# ClockGenerator.net
KiCad netlist of a schematic drawn in Altium Designer
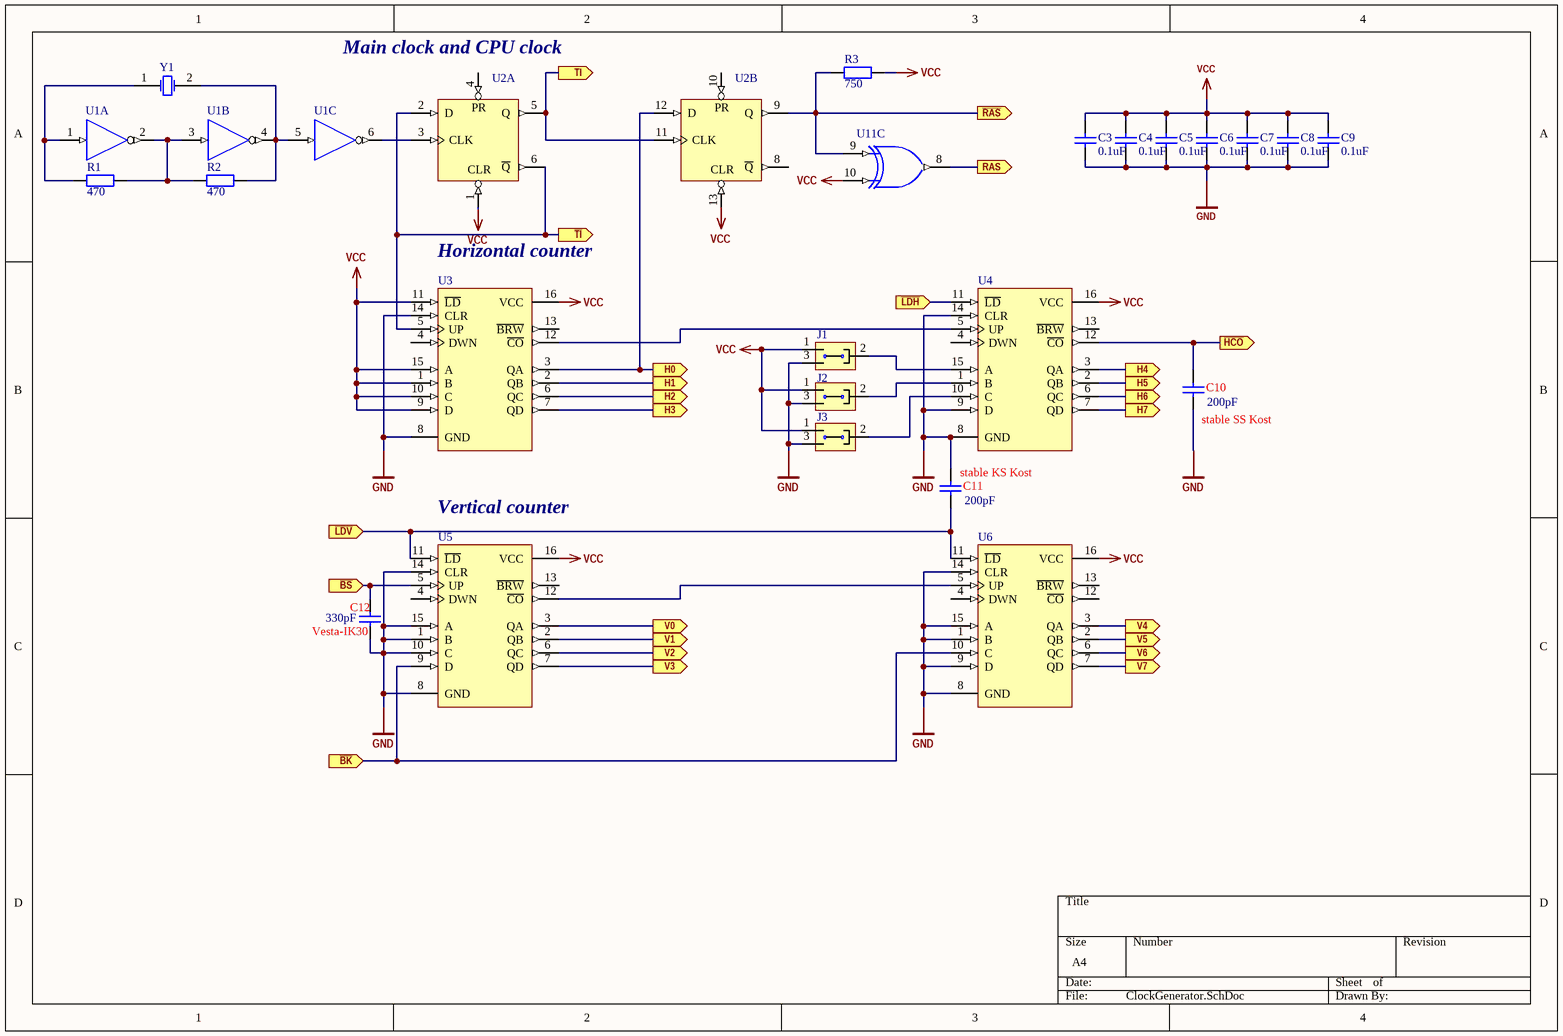
[diagram p0: ClockGenerator.SchDoc]

(export (version "E")
  (design (tool "Eeschema 10.0.6"))
  (components
    (comp (ref "C3")
      (value "0.1uF")
      (footprint "RAD-0.3")
      (description "Capacitor")
      (fields (field (name "Comment") "Cap") (field (name "PUBLISHER") "Altium Limited"))
      (libsource (lib "Lenin") (part "Cap"))
    )
    (comp (ref "C4")
      (value "0.1uF")
      (footprint "RAD-0.3")
      (description "Capacitor")
      (fields (field (name "Comment") "Cap") (field (name "PUBLISHER") "Altium Limited"))
      (libsource (lib "Lenin") (part "Cap"))
    )
    (comp (ref "C5")
      (value "0.1uF")
      (footprint "RAD-0.3")
      (description "Capacitor")
      (fields (field (name "Comment") "Cap") (field (name "PUBLISHER") "Altium Limited"))
      (libsource (lib "Lenin") (part "Cap"))
    )
    (comp (ref "C6")
      (value "0.1uF")
      (footprint "RAD-0.3")
      (description "Capacitor")
      (fields (field (name "Comment") "Cap") (field (name "PUBLISHER") "Altium Limited"))
      (libsource (lib "Lenin") (part "Cap"))
    )
    (comp (ref "C7")
      (value "0.1uF")
      (footprint "RAD-0.3")
      (description "Capacitor")
      (fields (field (name "Comment") "Cap") (field (name "PUBLISHER") "Altium Limited"))
      (libsource (lib "Lenin") (part "Cap"))
    )
    (comp (ref "C8")
      (value "0.1uF")
      (footprint "RAD-0.3")
      (description "Capacitor")
      (fields (field (name "Comment") "Cap") (field (name "PUBLISHER") "Altium Limited"))
      (libsource (lib "Lenin") (part "Cap"))
    )
    (comp (ref "C9")
      (value "0.1uF")
      (footprint "RAD-0.3")
      (description "Capacitor")
      (fields (field (name "Comment") "Cap") (field (name "PUBLISHER") "Altium Limited"))
      (libsource (lib "Lenin") (part "Cap"))
    )
    (comp (ref "C10")
      (value "stable SS Kost")
      (footprint "RAD-0.3")
      (description "Capacitor")
      (fields (field (name "ALTIUM_VALUE") "200pF") (field (name "PUBLISHER") "Altium Limited"))
      (libsource (lib "Lenin") (part "Cap"))
    )
    (comp (ref "C11")
      (value "stable KS Kost")
      (footprint "RAD-0.3")
      (description "Capacitor")
      (fields (field (name "ALTIUM_VALUE") "200pF") (field (name "PUBLISHER") "Altium Limited"))
      (libsource (lib "Lenin") (part "Cap"))
    )
    (comp (ref "C12")
      (value "Vesta-IK30")
      (footprint "RAD-0.3")
      (description "Capacitor")
      (fields (field (name "ALTIUM_VALUE") "330pF") (field (name "PUBLISHER") "Altium Limited"))
      (libsource (lib "Lenin") (part "Cap"))
    )
    (comp (ref "J1")
      (value "Jump3")
      (footprint "Miscellaneous Connectors:MHDR1X3")
      (libsource (lib "Lenin") (part "Jump3"))
    )
    (comp (ref "J2")
      (value "Jump3")
      (footprint "Miscellaneous Connectors:MHDR1X3")
      (libsource (lib "Lenin") (part "Jump3"))
    )
    (comp (ref "J3")
      (value "Jump3")
      (footprint "Miscellaneous Connectors:MHDR1X3")
      (libsource (lib "Lenin") (part "Jump3"))
    )
    (comp (ref "R1")
      (value "470")
      (footprint "Lenin:AXIAL-0.4")
      (description "Resistor")
      (fields (field (name "PUBLISHER") "Altium Limited"))
      (libsource (lib "Lenin") (part "Res2"))
    )
    (comp (ref "R2")
      (value "470")
      (footprint "Lenin:AXIAL-0.4")
      (description "Resistor")
      (fields (field (name "PUBLISHER") "Altium Limited"))
      (libsource (lib "Lenin") (part "Res2"))
    )
    (comp (ref "R3")
      (value "750")
      (footprint "Lenin:AXIAL-0.4")
      (description "Resistor")
      (fields (field (name "PUBLISHER") "Altium Limited"))
      (libsource (lib "Lenin") (part "Res2"))
    )
    (comp (ref "U1")
      (value "~")
      (footprint "N014")
      (description "Hex Inverter")
      (fields (field (name "PUBLISHER") "Altium Limited"))
      (libsource (lib "TI Logic Gate 2") (part "SN74HC04N"))
    )
    (comp (ref "U2")
      (value "~")
      (footprint "N014")
      (description "Dual D-Type Positive-Edge-Triggered Flip-Flop with Clear and Preset")
      (fields (field (name "PUBLISHER") "Altium Limited"))
      (libsource (lib "TI Logic Flip-Flop") (part "SN74HC74N"))
    )
    (comp (ref "U3")
      (value "~")
      (footprint "N016")
      (description "4-Bit Synchronous Up/Down Counter (Dual Clock with Clear)")
      (fields (field (name "PUBLISHER") "Altium Limited"))
      (libsource (lib "TI Logic Counter") (part "SN74HC193N"))
    )
    (comp (ref "U4")
      (value "~")
      (footprint "N016")
      (description "4-Bit Synchronous Up/Down Counter (Dual Clock with Clear)")
      (fields (field (name "PUBLISHER") "Altium Limited"))
      (libsource (lib "TI Logic Counter") (part "SN74HC193N"))
    )
    (comp (ref "U5")
      (value "~")
      (footprint "N016")
      (description "4-Bit Synchronous Up/Down Counter (Dual Clock with Clear)")
      (fields (field (name "PUBLISHER") "Altium Limited"))
      (libsource (lib "TI Logic Counter") (part "SN74HC193N"))
    )
    (comp (ref "U6")
      (value "~")
      (footprint "N016")
      (description "4-Bit Synchronous Up/Down Counter (Dual Clock with Clear)")
      (fields (field (name "PUBLISHER") "Altium Limited"))
      (libsource (lib "TI Logic Counter") (part "SN74HC193N"))
    )
    (comp (ref "U11")
      (value "~")
      (footprint "N014")
      (description "Quadruple 2-Input Exclusive-OR Gate")
      (fields (field (name "PUBLISHER") "Altium Limited"))
      (libsource (lib "TI Logic Gate 2") (part "SN74HC86N"))
    )
    (comp (ref "Y1")
      (value "XTAL")
      (footprint "Lenin:HC25U")
      (description "Crystal Oscillator")
      (fields (field (name "PUBLISHER") "Altium Limited"))
      (libsource (lib "Lenin") (part "XTAL"))
    )
  )
  (nets
    (net (code "1") (name "/H0") (class "Default")
      (node (ref "U2") (pin "12") (pinfunction "D_12") (pintype "input"))
      (node (ref "U3") (pin "3") (pinfunction "QA_3") (pintype "output"))
    )
    (net (code "2") (name "/H1") (class "Default")
      (node (ref "U3") (pin "2") (pinfunction "QB_2") (pintype "output"))
    )
    (net (code "3") (name "/H2") (class "Default")
      (node (ref "U3") (pin "6") (pinfunction "QC_6") (pintype "output"))
    )
    (net (code "4") (name "/H3") (class "Default")
      (node (ref "U3") (pin "7") (pinfunction "QD_7") (pintype "output"))
    )
    (net (code "5") (name "/H4") (class "Default")
      (node (ref "U4") (pin "3") (pinfunction "QA_3") (pintype "output"))
    )
    (net (code "6") (name "/H5") (class "Default")
      (node (ref "U4") (pin "2") (pinfunction "QB_2") (pintype "output"))
    )
    (net (code "7") (name "/H6") (class "Default")
      (node (ref "U4") (pin "6") (pinfunction "QC_6") (pintype "output"))
    )
    (net (code "8") (name "/H7") (class "Default")
      (node (ref "U4") (pin "7") (pinfunction "QD_7") (pintype "output"))
    )
    (net (code "9") (name "/RAS") (class "Default")
      (node (ref "U11") (pin "8") (pinfunction "Y_8") (pintype "output"))
    )
    (net (code "10") (name "/TI") (class "Default")
      (node (ref "U2") (pin "11") (pinfunction "CLK_11") (pintype "input"))
      (node (ref "U2") (pin "5") (pinfunction "Q_5") (pintype "output"))
    )
    (net (code "11") (name "/V0") (class "Default")
      (node (ref "U5") (pin "3") (pinfunction "QA_3") (pintype "output"))
    )
    (net (code "12") (name "/V1") (class "Default")
      (node (ref "U5") (pin "2") (pinfunction "QB_2") (pintype "output"))
    )
    (net (code "13") (name "/V2") (class "Default")
      (node (ref "U5") (pin "6") (pinfunction "QC_6") (pintype "output"))
    )
    (net (code "14") (name "/V3") (class "Default")
      (node (ref "U5") (pin "7") (pinfunction "QD_7") (pintype "output"))
    )
    (net (code "15") (name "/V4") (class "Default")
      (node (ref "U6") (pin "3") (pinfunction "QA_3") (pintype "output"))
    )
    (net (code "16") (name "/V5") (class "Default")
      (node (ref "U6") (pin "2") (pinfunction "QB_2") (pintype "output"))
    )
    (net (code "17") (name "/V6") (class "Default")
      (node (ref "U6") (pin "6") (pinfunction "QC_6") (pintype "output"))
    )
    (net (code "18") (name "/V7") (class "Default")
      (node (ref "U6") (pin "7") (pinfunction "QD_7") (pintype "output"))
    )
    (net (code "19") (name "/~{BK}") (class "Default")
      (node (ref "U5") (pin "9") (pinfunction "D_9") (pintype "input"))
      (node (ref "U6") (pin "10") (pinfunction "C_10") (pintype "input"))
    )
    (net (code "20") (name "/~{BS}") (class "Default")
      (node (ref "C12") (pin "2") (pinfunction "2_2") (pintype "passive"))
      (node (ref "U5") (pin "5") (pinfunction "UP_5") (pintype "input"))
    )
    (net (code "21") (name "/~{HCO}") (class "Default")
      (node (ref "C10") (pin "2") (pinfunction "2_2") (pintype "passive"))
      (node (ref "U4") (pin "12") (pinfunction "~{CO}_12") (pintype "output"))
    )
    (net (code "22") (name "/~{LDH}") (class "Default")
      (node (ref "U4") (pin "11") (pinfunction "~{LD}_11") (pintype "input"))
    )
    (net (code "23") (name "/~{LDV}") (class "Default")
      (node (ref "C11") (pin "1") (pinfunction "1_1") (pintype "passive"))
      (node (ref "U5") (pin "11") (pinfunction "~{LD}_11") (pintype "input"))
      (node (ref "U6") (pin "11") (pinfunction "~{LD}_11") (pintype "input"))
    )
    (net (code "24") (name "/~{RAS}") (class "Default")
      (node (ref "R3") (pin "1") (pinfunction "1_1") (pintype "passive"))
      (node (ref "U11") (pin "9") (pinfunction "A_9") (pintype "input"))
      (node (ref "U2") (pin "9") (pinfunction "Q_9") (pintype "output"))
    )
    (net (code "25") (name "/~{TI}") (class "Default")
      (node (ref "U2") (pin "2") (pinfunction "D_2") (pintype "input"))
      (node (ref "U2") (pin "6") (pinfunction "~{Q}_6") (pintype "output"))
      (node (ref "U3") (pin "5") (pinfunction "UP_5") (pintype "input"))
    )
    (net (code "26") (name "GND") (class "Default")
      (node (ref "C10") (pin "1") (pinfunction "1_1") (pintype "passive"))
      (node (ref "C11") (pin "2") (pinfunction "2_2") (pintype "passive"))
      (node (ref "C12") (pin "1") (pinfunction "1_1") (pintype "passive"))
      (node (ref "C3") (pin "1") (pinfunction "1_1") (pintype "passive"))
      (node (ref "C4") (pin "1") (pinfunction "1_1") (pintype "passive"))
      (node (ref "C5") (pin "1") (pinfunction "1_1") (pintype "passive"))
      (node (ref "C6") (pin "1") (pinfunction "1_1") (pintype "passive"))
      (node (ref "C7") (pin "1") (pinfunction "1_1") (pintype "passive"))
      (node (ref "C8") (pin "1") (pinfunction "1_1") (pintype "passive"))
      (node (ref "C9") (pin "1") (pinfunction "1_1") (pintype "passive"))
      (node (ref "J1") (pin "3") (pintype "passive"))
      (node (ref "J2") (pin "3") (pintype "passive"))
      (node (ref "J3") (pin "3") (pintype "passive"))
      (node (ref "U1") (pin "7") (pinfunction "GND_7") (pintype "power_in"))
      (node (ref "U11") (pin "7") (pinfunction "GND_7") (pintype "power_in"))
      (node (ref "U2") (pin "7") (pinfunction "GND_7") (pintype "power_in"))
      (node (ref "U3") (pin "14") (pinfunction "CLR_14") (pintype "input"))
      (node (ref "U3") (pin "8") (pinfunction "GND_8") (pintype "power_in"))
      (node (ref "U4") (pin "14") (pinfunction "CLR_14") (pintype "input"))
      (node (ref "U4") (pin "8") (pinfunction "GND_8") (pintype "power_in"))
      (node (ref "U4") (pin "9") (pinfunction "D_9") (pintype "input"))
      (node (ref "U5") (pin "1") (pinfunction "B_1") (pintype "input"))
      (node (ref "U5") (pin "10") (pinfunction "C_10") (pintype "input"))
      (node (ref "U5") (pin "14") (pinfunction "CLR_14") (pintype "input"))
      (node (ref "U5") (pin "15") (pinfunction "A_15") (pintype "input"))
      (node (ref "U5") (pin "8") (pinfunction "GND_8") (pintype "power_in"))
      (node (ref "U6") (pin "1") (pinfunction "B_1") (pintype "input"))
      (node (ref "U6") (pin "14") (pinfunction "CLR_14") (pintype "input"))
      (node (ref "U6") (pin "15") (pinfunction "A_15") (pintype "input"))
      (node (ref "U6") (pin "8") (pinfunction "GND_8") (pintype "power_in"))
      (node (ref "U6") (pin "9") (pinfunction "D_9") (pintype "input"))
    )
    (net (code "27") (name "Net-(U1A-A)") (class "Default")
      (node (ref "R1") (pin "1") (pinfunction "1_1") (pintype "passive"))
      (node (ref "U1") (pin "1") (pinfunction "A_1") (pintype "input"))
      (node (ref "Y1") (pin "1") (pinfunction "OSC1_1") (pintype "passive"))
    )
    (net (code "28") (name "Net-(U1A-Y)") (class "Default")
      (node (ref "R1") (pin "2") (pinfunction "2_2") (pintype "passive"))
      (node (ref "R2") (pin "1") (pinfunction "1_1") (pintype "passive"))
      (node (ref "U1") (pin "2") (pinfunction "Y_2") (pintype "output"))
      (node (ref "U1") (pin "3") (pinfunction "A_3") (pintype "input"))
    )
    (net (code "29") (name "Net-(U1B-Y)") (class "Default")
      (node (ref "R2") (pin "2") (pinfunction "2_2") (pintype "passive"))
      (node (ref "U1") (pin "4") (pinfunction "Y_4") (pintype "output"))
      (node (ref "U1") (pin "5") (pinfunction "A_5") (pintype "input"))
      (node (ref "Y1") (pin "2") (pinfunction "OSC2_2") (pintype "passive"))
    )
    (net (code "30") (name "Net-(U1C-Y)") (class "Default")
      (node (ref "U1") (pin "6") (pinfunction "Y_6") (pintype "output"))
      (node (ref "U2") (pin "3") (pinfunction "CLK_3") (pintype "input"))
    )
    (net (code "31") (name "Net-(U3-~{CO})") (class "Default")
      (node (ref "U3") (pin "12") (pinfunction "~{CO}_12") (pintype "output"))
      (node (ref "U4") (pin "5") (pinfunction "UP_5") (pintype "input"))
    )
    (net (code "32") (name "Net-(U4-A)") (class "Default")
      (node (ref "J1") (pin "2") (pintype "passive"))
      (node (ref "U4") (pin "15") (pinfunction "A_15") (pintype "input"))
    )
    (net (code "33") (name "Net-(U4-B)") (class "Default")
      (node (ref "J2") (pin "2") (pintype "passive"))
      (node (ref "U4") (pin "1") (pinfunction "B_1") (pintype "input"))
    )
    (net (code "34") (name "Net-(U4-C)") (class "Default")
      (node (ref "J3") (pin "2") (pintype "passive"))
      (node (ref "U4") (pin "10") (pinfunction "C_10") (pintype "input"))
    )
    (net (code "35") (name "Net-(U5-~{CO})") (class "Default")
      (node (ref "U5") (pin "12") (pinfunction "~{CO}_12") (pintype "output"))
      (node (ref "U6") (pin "5") (pinfunction "UP_5") (pintype "input"))
    )
    (net (code "36") (name "VCC") (class "Default")
      (node (ref "C3") (pin "2") (pinfunction "2_2") (pintype "passive"))
      (node (ref "C4") (pin "2") (pinfunction "2_2") (pintype "passive"))
      (node (ref "C5") (pin "2") (pinfunction "2_2") (pintype "passive"))
      (node (ref "C6") (pin "2") (pinfunction "2_2") (pintype "passive"))
      (node (ref "C7") (pin "2") (pinfunction "2_2") (pintype "passive"))
      (node (ref "C8") (pin "2") (pinfunction "2_2") (pintype "passive"))
      (node (ref "C9") (pin "2") (pinfunction "2_2") (pintype "passive"))
      (node (ref "J1") (pin "1") (pintype "passive"))
      (node (ref "J2") (pin "1") (pintype "passive"))
      (node (ref "J3") (pin "1") (pintype "passive"))
      (node (ref "R3") (pin "2") (pinfunction "2_2") (pintype "passive"))
      (node (ref "U1") (pin "14") (pinfunction "VCC_14") (pintype "power_in"))
      (node (ref "U11") (pin "10") (pinfunction "B_10") (pintype "input"))
      (node (ref "U11") (pin "14") (pinfunction "VCC_14") (pintype "power_in"))
      (node (ref "U2") (pin "1") (pinfunction "CLR_1") (pintype "input"))
      (node (ref "U2") (pin "13") (pinfunction "CLR_13") (pintype "input"))
      (node (ref "U2") (pin "14") (pinfunction "VCC_14") (pintype "power_in"))
      (node (ref "U3") (pin "1") (pinfunction "B_1") (pintype "input"))
      (node (ref "U3") (pin "10") (pinfunction "C_10") (pintype "input"))
      (node (ref "U3") (pin "11") (pinfunction "~{LD}_11") (pintype "input"))
      (node (ref "U3") (pin "15") (pinfunction "A_15") (pintype "input"))
      (node (ref "U3") (pin "16") (pinfunction "VCC_16") (pintype "power_in"))
      (node (ref "U3") (pin "9") (pinfunction "D_9") (pintype "input"))
      (node (ref "U4") (pin "16") (pinfunction "VCC_16") (pintype "power_in"))
      (node (ref "U5") (pin "16") (pinfunction "VCC_16") (pintype "power_in"))
      (node (ref "U6") (pin "16") (pinfunction "VCC_16") (pintype "power_in"))
    )
    (net (code "37") (name "unconnected-(U2A-PR-Pad4)") (class "Default")
      (node (ref "U2") (pin "4") (pinfunction "PR_4") (pintype "input"))
    )
    (net (code "38") (name "unconnected-(U2B-PR-Pad10)") (class "Default")
      (node (ref "U2") (pin "10") (pinfunction "PR_10") (pintype "input"))
    )
    (net (code "39") (name "unconnected-(U2B-~{Q}-Pad8)") (class "Default")
      (node (ref "U2") (pin "8") (pinfunction "~{Q}_8") (pintype "output"))
    )
    (net (code "40") (name "unconnected-(U3-DWN-Pad4)") (class "Default")
      (node (ref "U3") (pin "4") (pinfunction "DWN_4") (pintype "input"))
    )
    (net (code "41") (name "unconnected-(U3-~{BRW}-Pad13)") (class "Default")
      (node (ref "U3") (pin "13") (pinfunction "~{BRW}_13") (pintype "output"))
    )
    (net (code "42") (name "unconnected-(U4-DWN-Pad4)") (class "Default")
      (node (ref "U4") (pin "4") (pinfunction "DWN_4") (pintype "input"))
    )
    (net (code "43") (name "unconnected-(U4-~{BRW}-Pad13)") (class "Default")
      (node (ref "U4") (pin "13") (pinfunction "~{BRW}_13") (pintype "output"))
    )
    (net (code "44") (name "unconnected-(U5-DWN-Pad4)") (class "Default")
      (node (ref "U5") (pin "4") (pinfunction "DWN_4") (pintype "input"))
    )
    (net (code "45") (name "unconnected-(U5-~{BRW}-Pad13)") (class "Default")
      (node (ref "U5") (pin "13") (pinfunction "~{BRW}_13") (pintype "output"))
    )
    (net (code "46") (name "unconnected-(U6-DWN-Pad4)") (class "Default")
      (node (ref "U6") (pin "4") (pinfunction "DWN_4") (pintype "input"))
    )
    (net (code "47") (name "unconnected-(U6-~{BRW}-Pad13)") (class "Default")
      (node (ref "U6") (pin "13") (pinfunction "~{BRW}_13") (pintype "output"))
    )
    (net (code "48") (name "unconnected-(U6-~{CO}-Pad12)") (class "Default")
      (node (ref "U6") (pin "12") (pinfunction "~{CO}_12") (pintype "output"))
    )
  )
)
